# 04-Power_Stage.net
KiCad netlist of a schematic drawn in Altium Designer
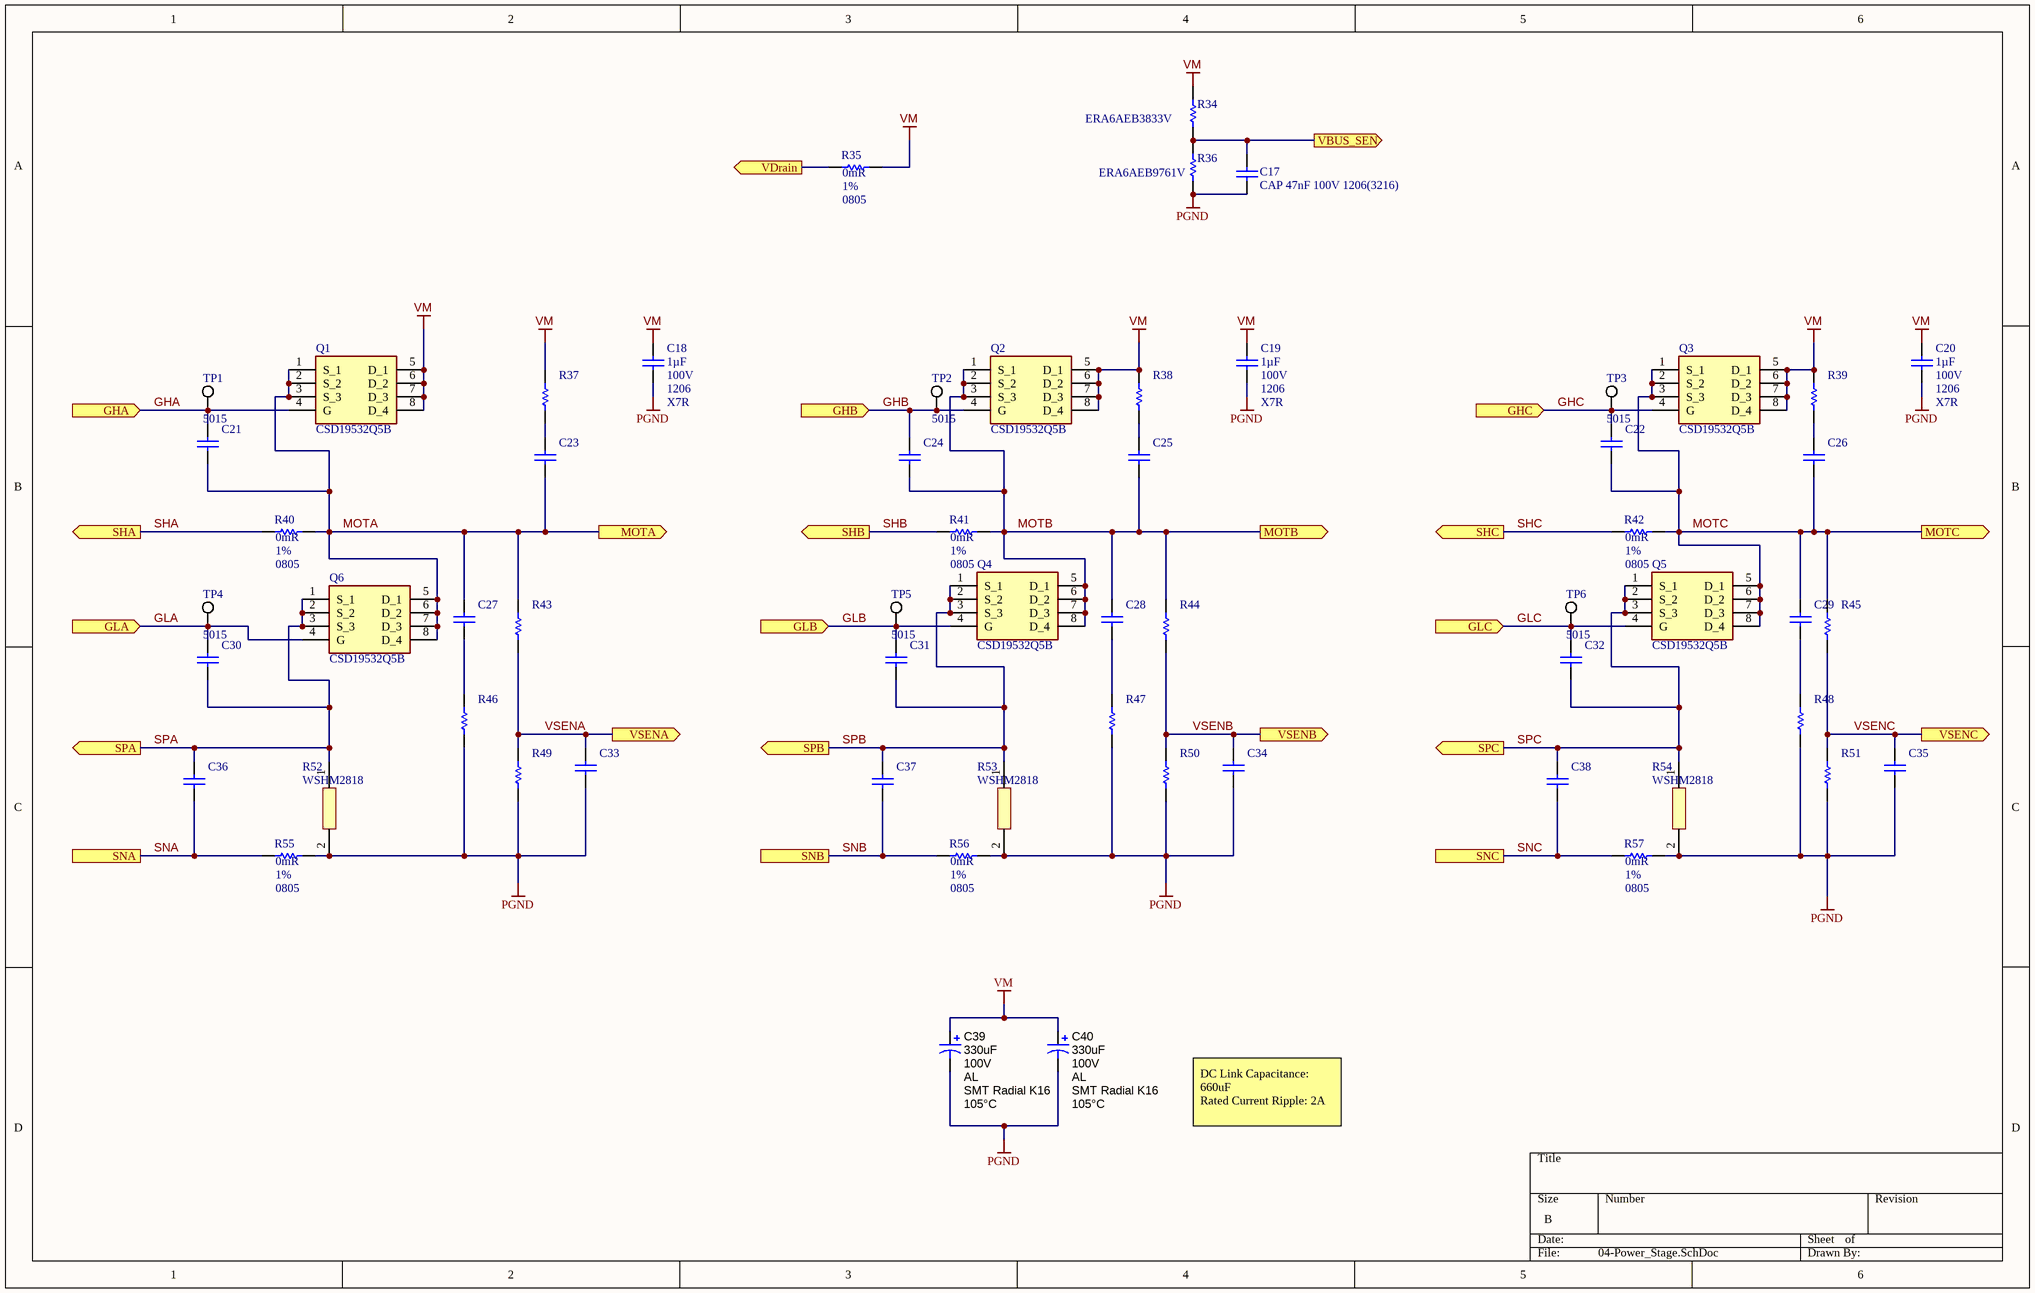
[diagram p0: 04-Power_Stage.SchDoc]

(export (version "E")
  (design (tool "Eeschema 10.0.6"))
  (components
    (comp (ref "C17")
      (value "CAP 47nF 100V 1206(3216)")
      (footprint "CAPC1206(3216)170_N")
      (description "CAP 47nF 100V ±10% 1206 (3216 Metric) Thickness 1.7mm SMD")
      (fields (field (name "TOLERANCE") "Â±10%"))
      (libsource (lib "Altium Content Vault") (part "CAP"))
    )
    (comp (ref "C18")
      (value "C3216X7R2A105K160AA")
      (footprint "CAPC3216X180X20LL20")
      (description "Chip Capacitor, 1 uF, +/- 10%, 100 V, -55 to 125 degC, 1206 (3216 Metric), RoHS, Tape and Reel")
      (fields
        (field (name "CAPACITANCE") "1µF")
        (field (name "MANUFACTURER") "TDK")
        (field (name "PACKAGE REFERENCE") "1206")
        (field (name "VOLTAGE - RATED") "100V")
        (field (name "TOLERANCE") "±10%")
        (field (name "TEMPERATURE COEFFICIENT") "X7R")
      )
      (libsource (lib "Altium Content Vault") (part "CAP-NP-2"))
    )
    (comp (ref "C19")
      (value "C3216X7R2A105K160AA")
      (footprint "CAPC3216X180X20LL20")
      (description "Chip Capacitor, 1 uF, +/- 10%, 100 V, -55 to 125 degC, 1206 (3216 Metric), RoHS, Tape and Reel")
      (fields
        (field (name "CAPACITANCE") "1µF")
        (field (name "MANUFACTURER") "TDK")
        (field (name "PACKAGE REFERENCE") "1206")
        (field (name "VOLTAGE - RATED") "100V")
        (field (name "TOLERANCE") "±10%")
        (field (name "TEMPERATURE COEFFICIENT") "X7R")
      )
      (libsource (lib "Altium Content Vault") (part "CAP-NP-2"))
    )
    (comp (ref "C20")
      (value "C3216X7R2A105K160AA")
      (footprint "CAPC3216X180X20LL20")
      (description "Chip Capacitor, 1 uF, +/- 10%, 100 V, -55 to 125 degC, 1206 (3216 Metric), RoHS, Tape and Reel")
      (fields
        (field (name "CAPACITANCE") "1µF")
        (field (name "MANUFACTURER") "TDK")
        (field (name "PACKAGE REFERENCE") "1206")
        (field (name "VOLTAGE - RATED") "100V")
        (field (name "TOLERANCE") "±10%")
        (field (name "TEMPERATURE COEFFICIENT") "X7R")
      )
      (libsource (lib "Altium Content Vault") (part "CAP-NP-2"))
    )
    (comp (ref "C21")
      (value "GRM188R72A222KA01D")
      (footprint "CAPC1608X90X35NL10T15")
      (fields (field (name "MANUFACTURER") "Murata"))
      (libsource (lib "Altium Content Vault") (part "CAP"))
    )
    (comp (ref "C22")
      (value "GRM188R72A222KA01D")
      (footprint "CAPC1608X90X35NL10T15")
      (fields (field (name "MANUFACTURER") "Murata"))
      (libsource (lib "Altium Content Vault") (part "CAP"))
    )
    (comp (ref "C23")
      (value "GRM188R72A222KA01D")
      (footprint "CAPC1608X90X35NL10T15")
      (fields (field (name "MANUFACTURER") "Murata"))
      (libsource (lib "Altium Content Vault") (part "CAP"))
    )
    (comp (ref "C24")
      (value "GRM188R72A222KA01D")
      (footprint "CAPC1608X90X35NL10T15")
      (fields (field (name "MANUFACTURER") "Murata"))
      (libsource (lib "Altium Content Vault") (part "CAP"))
    )
    (comp (ref "C25")
      (value "GRM188R72A222KA01D")
      (footprint "CAPC1608X90X35NL10T15")
      (fields (field (name "MANUFACTURER") "Murata"))
      (libsource (lib "Altium Content Vault") (part "CAP"))
    )
    (comp (ref "C26")
      (value "GRM188R72A222KA01D")
      (footprint "CAPC1608X90X35NL10T15")
      (fields (field (name "MANUFACTURER") "Murata"))
      (libsource (lib "Altium Content Vault") (part "CAP"))
    )
    (comp (ref "C27")
      (value "GRM188R72A222KA01D")
      (footprint "CAPC1608X90X35NL10T15")
      (fields (field (name "MANUFACTURER") "Murata"))
      (libsource (lib "Altium Content Vault") (part "CAP"))
    )
    (comp (ref "C28")
      (value "GRM188R72A222KA01D")
      (footprint "CAPC1608X90X35NL10T15")
      (fields (field (name "MANUFACTURER") "Murata"))
      (libsource (lib "Altium Content Vault") (part "CAP"))
    )
    (comp (ref "C29")
      (value "GRM188R72A222KA01D")
      (footprint "CAPC1608X90X35NL10T15")
      (fields (field (name "MANUFACTURER") "Murata"))
      (libsource (lib "Altium Content Vault") (part "CAP"))
    )
    (comp (ref "C30")
      (value "GRM188R72A222KA01D")
      (footprint "CAPC1608X90X35NL10T15")
      (fields (field (name "MANUFACTURER") "Murata"))
      (libsource (lib "Altium Content Vault") (part "CAP"))
    )
    (comp (ref "C31")
      (value "GRM188R72A222KA01D")
      (footprint "CAPC1608X90X35NL10T15")
      (fields (field (name "MANUFACTURER") "Murata"))
      (libsource (lib "Altium Content Vault") (part "CAP"))
    )
    (comp (ref "C32")
      (value "GRM188R72A222KA01D")
      (footprint "CAPC1608X90X35NL10T15")
      (fields (field (name "MANUFACTURER") "Murata"))
      (libsource (lib "Altium Content Vault") (part "CAP"))
    )
    (comp (ref "C33")
      (value "06033C473JAT2A")
      (footprint "CAPC1608X90X35NL15T15")
      (fields (field (name "MANUFACTURER") "AVX Interconnect / Elco"))
      (libsource (lib "Altium Content Vault") (part "CAP"))
    )
    (comp (ref "C34")
      (value "06033C473JAT2A")
      (footprint "CAPC1608X90X35NL15T15")
      (fields (field (name "MANUFACTURER") "AVX Interconnect / Elco"))
      (libsource (lib "Altium Content Vault") (part "CAP"))
    )
    (comp (ref "C35")
      (value "06033C473JAT2A")
      (footprint "CAPC1608X90X35NL15T15")
      (fields (field (name "MANUFACTURER") "AVX Interconnect / Elco"))
      (libsource (lib "Altium Content Vault") (part "CAP"))
    )
    (comp (ref "C36")
      (value "0603YC102KAT2A")
      (footprint "CAPC1608X90X35NL15T15")
      (fields (field (name "MANUFACTURER") "AVX Interconnect / Elco"))
      (libsource (lib "Altium Content Vault") (part "CAP"))
    )
    (comp (ref "C37")
      (value "0603YC102KAT2A")
      (footprint "CAPC1608X90X35NL15T15")
      (fields (field (name "MANUFACTURER") "AVX Interconnect / Elco"))
      (libsource (lib "Altium Content Vault") (part "CAP"))
    )
    (comp (ref "C38")
      (value "0603YC102KAT2A")
      (footprint "CAPC1608X90X35NL15T15")
      (fields (field (name "MANUFACTURER") "AVX Interconnect / Elco"))
      (libsource (lib "Altium Content Vault") (part "CAP"))
    )
    (comp (ref "C39")
      (value "EEV-FK2A331M")
      (footprint "SM_RADIAL_K16")
      (description "CAP, AL, 330 uF, 100 V, +/- 20%, 0.153 ohm, AEC-Q200 Grade 2, SMD")
      (fields
        (field (name "TAMAX_C") "105°C")
        (field (name "MANUFACTURER") "Panasonic")
        (field (name "PACKAGEREFERENCE") "SMT Radial K16")
        (field (name "VDC_V") "100V")
        (field (name "TECHNOLOGY") "AL")
        (field (name "VALUEDISPLAYED") "330uF")
        (field (name "PUBLISHER") "Texas Instruments")
      )
      (libsource (lib "driver_board_lib") (part "CMP-0011224-2"))
    )
    (comp (ref "C40")
      (value "EEV-FK2A331M")
      (footprint "SM_RADIAL_K16")
      (description "CAP, AL, 330 uF, 100 V, +/- 20%, 0.153 ohm, AEC-Q200 Grade 2, SMD")
      (fields
        (field (name "TAMAX_C") "105°C")
        (field (name "MANUFACTURER") "Panasonic")
        (field (name "PACKAGEREFERENCE") "SMT Radial K16")
        (field (name "VDC_V") "100V")
        (field (name "TECHNOLOGY") "AL")
        (field (name "VALUEDISPLAYED") "330uF")
        (field (name "PUBLISHER") "Texas Instruments")
      )
      (libsource (lib "driver_board_lib") (part "CMP-0011224-2"))
    )
    (comp (ref "Q1")
      (value "CSD19532Q5B")
      (footprint "SamacSys:Q5B")
      (description "Transistor")
      (fields (field (name "MOUSER PART NUMBER") "595-CSD19532Q5B"))
      (libsource (lib "*") (part "CSD19532Q5B"))
    )
    (comp (ref "Q2")
      (value "CSD19532Q5B")
      (footprint "SamacSys:Q5B")
      (description "Transistor")
      (fields (field (name "MOUSER PART NUMBER") "595-CSD19532Q5B"))
      (libsource (lib "*") (part "CSD19532Q5B"))
    )
    (comp (ref "Q3")
      (value "CSD19532Q5B")
      (footprint "SamacSys:Q5B")
      (description "Transistor")
      (fields (field (name "MOUSER PART NUMBER") "595-CSD19532Q5B"))
      (libsource (lib "*") (part "CSD19532Q5B"))
    )
    (comp (ref "Q4")
      (value "CSD19532Q5B")
      (footprint "SamacSys:Q5B")
      (description "Transistor")
      (fields (field (name "MOUSER PART NUMBER") "595-CSD19532Q5B"))
      (libsource (lib "*") (part "CSD19532Q5B"))
    )
    (comp (ref "Q5")
      (value "CSD19532Q5B")
      (footprint "SamacSys:Q5B")
      (description "Transistor")
      (fields (field (name "MOUSER PART NUMBER") "595-CSD19532Q5B"))
      (libsource (lib "*") (part "CSD19532Q5B"))
    )
    (comp (ref "Q6")
      (value "CSD19532Q5B")
      (footprint "SamacSys:Q5B")
      (description "Transistor")
      (fields (field (name "MOUSER PART NUMBER") "595-CSD19532Q5B"))
      (libsource (lib "*") (part "CSD19532Q5B"))
    )
    (comp (ref "R34")
      (value "ERA6AEB3833V")
      (footprint "RESC2013X60X40LL20T25")
      (fields (field (name "MANUFACTURER") "Panasonic"))
      (libsource (lib "Altium Content Vault") (part "RES"))
    )
    (comp (ref "R35")
      (value "CRCW08050000Z0EA")
      (footprint "RESC2013X50X30LL20T20")
      (fields
        (field (name "MANUFACTURER") "Vishay Dale")
        (field (name "CASE CODE (IMPERIAL)") "0805")
        (field (name "RESISTANCE") "0mR")
        (field (name "TOLERANCE") "1%")
      )
      (libsource (lib "Altium Content Vault") (part "RES"))
    )
    (comp (ref "R36")
      (value "ERA6AEB9761V")
      (footprint "RESC2013X60X40NL20T25")
      (fields (field (name "MANUFACTURER") "Panasonic"))
      (libsource (lib "Altium Content Vault") (part "RES"))
    )
    (comp (ref "R37")
      (value "CRCW08052R70JNEA")
      (footprint "RESC2013X50X30NL20T20")
      (fields (field (name "MANUFACTURER") "Vishay Dale"))
      (libsource (lib "Altium Content Vault") (part "RES"))
    )
    (comp (ref "R38")
      (value "CRCW08052R70JNEA")
      (footprint "RESC2013X50X30NL20T20")
      (fields (field (name "MANUFACTURER") "Vishay Dale"))
      (libsource (lib "Altium Content Vault") (part "RES"))
    )
    (comp (ref "R39")
      (value "CRCW08052R70JNEA")
      (footprint "RESC2013X50X30NL20T20")
      (fields (field (name "MANUFACTURER") "Vishay Dale"))
      (libsource (lib "Altium Content Vault") (part "RES"))
    )
    (comp (ref "R40")
      (value "CRCW08050000Z0EA")
      (footprint "RESC2013X50X30LL20T20")
      (fields
        (field (name "MANUFACTURER") "Vishay Dale")
        (field (name "CASE CODE (IMPERIAL)") "0805")
        (field (name "RESISTANCE") "0mR")
        (field (name "TOLERANCE") "1%")
      )
      (libsource (lib "Altium Content Vault") (part "RES"))
    )
    (comp (ref "R41")
      (value "CRCW08050000Z0EA")
      (footprint "RESC2013X50X30LL20T20")
      (fields
        (field (name "MANUFACTURER") "Vishay Dale")
        (field (name "CASE CODE (IMPERIAL)") "0805")
        (field (name "RESISTANCE") "0mR")
        (field (name "TOLERANCE") "1%")
      )
      (libsource (lib "Altium Content Vault") (part "RES"))
    )
    (comp (ref "R42")
      (value "CRCW08050000Z0EA")
      (footprint "RESC2013X50X30LL20T20")
      (fields
        (field (name "MANUFACTURER") "Vishay Dale")
        (field (name "CASE CODE (IMPERIAL)") "0805")
        (field (name "RESISTANCE") "0mR")
        (field (name "TOLERANCE") "1%")
      )
      (libsource (lib "Altium Content Vault") (part "RES"))
    )
    (comp (ref "R43")
      (value "CRCW0603383KFKEA")
      (footprint "RESC1609X50X30ML10T20")
      (fields (field (name "MANUFACTURER") "Vishay Dale"))
      (libsource (lib "Altium Content Vault") (part "RES"))
    )
    (comp (ref "R44")
      (value "CRCW0603383KFKEA")
      (footprint "RESC1609X50X30ML10T20")
      (fields (field (name "MANUFACTURER") "Vishay Dale"))
      (libsource (lib "Altium Content Vault") (part "RES"))
    )
    (comp (ref "R45")
      (value "CRCW0603383KFKEA")
      (footprint "RESC1609X50X30ML10T20")
      (fields (field (name "MANUFACTURER") "Vishay Dale"))
      (libsource (lib "Altium Content Vault") (part "RES"))
    )
    (comp (ref "R46")
      (value "CRCW08052R70JNEA")
      (footprint "RESC2013X50X30NL20T20")
      (fields (field (name "MANUFACTURER") "Vishay Dale"))
      (libsource (lib "Altium Content Vault") (part "RES"))
    )
    (comp (ref "R47")
      (value "CRCW08052R70JNEA")
      (footprint "RESC2013X50X30NL20T20")
      (fields (field (name "MANUFACTURER") "Vishay Dale"))
      (libsource (lib "Altium Content Vault") (part "RES"))
    )
    (comp (ref "R48")
      (value "CRCW08052R70JNEA")
      (footprint "RESC2013X50X30NL20T20")
      (fields (field (name "MANUFACTURER") "Vishay Dale"))
      (libsource (lib "Altium Content Vault") (part "RES"))
    )
    (comp (ref "R49")
      (value "RC0603FR-079K76L")
      (footprint "RESC1608X55X25NL10T15")
      (fields (field (name "MANUFACTURER") "Yageo"))
      (libsource (lib "Altium Content Vault") (part "RES"))
    )
    (comp (ref "R50")
      (value "RC0603FR-079K76L")
      (footprint "RESC1608X55X25NL10T15")
      (fields (field (name "MANUFACTURER") "Yageo"))
      (libsource (lib "Altium Content Vault") (part "RES"))
    )
    (comp (ref "R51")
      (value "RC0603FR-079K76L")
      (footprint "RESC1608X55X25NL10T15")
      (fields (field (name "MANUFACTURER") "Yageo"))
      (libsource (lib "Altium Content Vault") (part "RES"))
    )
    (comp (ref "R52")
      (value "WSHM2818")
      (footprint "WSHM2818:PCBComponent_1")
      (libsource (lib "WSHM2818") (part "WSHM2818"))
    )
    (comp (ref "R53")
      (value "WSHM2818")
      (footprint "WSHM2818:PCBComponent_1")
      (libsource (lib "WSHM2818") (part "WSHM2818"))
    )
    (comp (ref "R54")
      (value "WSHM2818")
      (footprint "WSHM2818:PCBComponent_1")
      (libsource (lib "WSHM2818") (part "WSHM2818"))
    )
    (comp (ref "R55")
      (value "CRCW08050000Z0EA")
      (footprint "RESC2013X50X30LL20T20")
      (fields
        (field (name "MANUFACTURER") "Vishay Dale")
        (field (name "CASE CODE (IMPERIAL)") "0805")
        (field (name "RESISTANCE") "0mR")
        (field (name "TOLERANCE") "1%")
      )
      (libsource (lib "Altium Content Vault") (part "RES"))
    )
    (comp (ref "R56")
      (value "CRCW08050000Z0EA")
      (footprint "RESC2013X50X30LL20T20")
      (fields
        (field (name "MANUFACTURER") "Vishay Dale")
        (field (name "CASE CODE (IMPERIAL)") "0805")
        (field (name "RESISTANCE") "0mR")
        (field (name "TOLERANCE") "1%")
      )
      (libsource (lib "Altium Content Vault") (part "RES"))
    )
    (comp (ref "R57")
      (value "CRCW08050000Z0EA")
      (footprint "RESC2013X50X30LL20T20")
      (fields
        (field (name "MANUFACTURER") "Vishay Dale")
        (field (name "CASE CODE (IMPERIAL)") "0805")
        (field (name "RESISTANCE") "0mR")
        (field (name "TOLERANCE") "1%")
      )
      (libsource (lib "Altium Content Vault") (part "RES"))
    )
    (comp (ref "TP1")
      (value "5015")
      (footprint "KSTN-5015_V")
      (description "Test Point, White, SMT")
      (fields (field (name "MANUFACTURER") "Keystone"))
      (libsource (lib "Altium Content Vault") (part "TESTPOINT_WHITE"))
    )
    (comp (ref "TP2")
      (value "5015")
      (footprint "KSTN-5015_V")
      (description "Test Point, White, SMT")
      (fields (field (name "MANUFACTURER") "Keystone"))
      (libsource (lib "Altium Content Vault") (part "TESTPOINT_WHITE"))
    )
    (comp (ref "TP3")
      (value "5015")
      (footprint "KSTN-5015_V")
      (description "Test Point, White, SMT")
      (fields (field (name "MANUFACTURER") "Keystone"))
      (libsource (lib "Altium Content Vault") (part "TESTPOINT_WHITE"))
    )
    (comp (ref "TP4")
      (value "5015")
      (footprint "KSTN-5015_V")
      (description "Test Point, White, SMT")
      (fields (field (name "MANUFACTURER") "Keystone"))
      (libsource (lib "Altium Content Vault") (part "TESTPOINT_WHITE"))
    )
    (comp (ref "TP5")
      (value "5015")
      (footprint "KSTN-5015_V")
      (description "Test Point, White, SMT")
      (fields (field (name "MANUFACTURER") "Keystone"))
      (libsource (lib "Altium Content Vault") (part "TESTPOINT_WHITE"))
    )
    (comp (ref "TP6")
      (value "5015")
      (footprint "KSTN-5015_V")
      (description "Test Point, White, SMT")
      (fields (field (name "MANUFACTURER") "Keystone"))
      (libsource (lib "Altium Content Vault") (part "TESTPOINT_WHITE"))
    )
  )
  (nets
    (net (code "1") (name "/GHA") (class "Default")
      (node (ref "C21") (pin "2") (pinfunction "2_2") (pintype "passive"))
      (node (ref "Q1") (pin "4") (pinfunction "G_4") (pintype "passive"))
      (node (ref "TP1") (pin "1") (pinfunction "1_1") (pintype "passive"))
    )
    (net (code "2") (name "/GHB") (class "Default")
      (node (ref "C24") (pin "2") (pinfunction "2_2") (pintype "passive"))
      (node (ref "Q2") (pin "4") (pinfunction "G_4") (pintype "passive"))
      (node (ref "TP2") (pin "1") (pinfunction "1_1") (pintype "passive"))
    )
    (net (code "3") (name "/GHC") (class "Default")
      (node (ref "C22") (pin "2") (pinfunction "2_2") (pintype "passive"))
      (node (ref "Q3") (pin "4") (pinfunction "G_4") (pintype "passive"))
      (node (ref "TP3") (pin "1") (pinfunction "1_1") (pintype "passive"))
    )
    (net (code "4") (name "/GLA") (class "Default")
      (node (ref "C30") (pin "2") (pinfunction "2_2") (pintype "passive"))
      (node (ref "Q6") (pin "4") (pinfunction "G_4") (pintype "passive"))
      (node (ref "TP4") (pin "1") (pinfunction "1_1") (pintype "passive"))
    )
    (net (code "5") (name "/GLB") (class "Default")
      (node (ref "C31") (pin "2") (pinfunction "2_2") (pintype "passive"))
      (node (ref "Q4") (pin "4") (pinfunction "G_4") (pintype "passive"))
      (node (ref "TP5") (pin "1") (pinfunction "1_1") (pintype "passive"))
    )
    (net (code "6") (name "/GLC") (class "Default")
      (node (ref "C32") (pin "2") (pinfunction "2_2") (pintype "passive"))
      (node (ref "Q5") (pin "4") (pinfunction "G_4") (pintype "passive"))
      (node (ref "TP6") (pin "1") (pinfunction "1_1") (pintype "passive"))
    )
    (net (code "7") (name "/MOTA") (class "Default")
      (node (ref "C21") (pin "1") (pinfunction "1_1") (pintype "passive"))
      (node (ref "C23") (pin "1") (pinfunction "1_1") (pintype "passive"))
      (node (ref "C27") (pin "2") (pinfunction "2_2") (pintype "passive"))
      (node (ref "Q1") (pin "1") (pinfunction "S_1_1") (pintype "passive"))
      (node (ref "Q1") (pin "2") (pinfunction "S_2_2") (pintype "passive"))
      (node (ref "Q1") (pin "3") (pinfunction "S_3_3") (pintype "passive"))
      (node (ref "Q6") (pin "5") (pinfunction "D_1_5") (pintype "passive"))
      (node (ref "Q6") (pin "6") (pinfunction "D_2_6") (pintype "passive"))
      (node (ref "Q6") (pin "7") (pinfunction "D_3_7") (pintype "passive"))
      (node (ref "Q6") (pin "8") (pinfunction "D_4_8") (pintype "passive"))
      (node (ref "R40") (pin "2") (pinfunction "2_2") (pintype "passive"))
      (node (ref "R43") (pin "2") (pinfunction "2_2") (pintype "passive"))
    )
    (net (code "8") (name "/MOTB") (class "Default")
      (node (ref "C24") (pin "1") (pinfunction "1_1") (pintype "passive"))
      (node (ref "C25") (pin "1") (pinfunction "1_1") (pintype "passive"))
      (node (ref "C28") (pin "2") (pinfunction "2_2") (pintype "passive"))
      (node (ref "Q2") (pin "1") (pinfunction "S_1_1") (pintype "passive"))
      (node (ref "Q2") (pin "2") (pinfunction "S_2_2") (pintype "passive"))
      (node (ref "Q2") (pin "3") (pinfunction "S_3_3") (pintype "passive"))
      (node (ref "Q4") (pin "5") (pinfunction "D_1_5") (pintype "passive"))
      (node (ref "Q4") (pin "6") (pinfunction "D_2_6") (pintype "passive"))
      (node (ref "Q4") (pin "7") (pinfunction "D_3_7") (pintype "passive"))
      (node (ref "Q4") (pin "8") (pinfunction "D_4_8") (pintype "passive"))
      (node (ref "R41") (pin "2") (pinfunction "2_2") (pintype "passive"))
      (node (ref "R44") (pin "2") (pinfunction "2_2") (pintype "passive"))
    )
    (net (code "9") (name "/MOTC") (class "Default")
      (node (ref "C22") (pin "1") (pinfunction "1_1") (pintype "passive"))
      (node (ref "C26") (pin "1") (pinfunction "1_1") (pintype "passive"))
      (node (ref "C29") (pin "2") (pinfunction "2_2") (pintype "passive"))
      (node (ref "Q3") (pin "1") (pinfunction "S_1_1") (pintype "passive"))
      (node (ref "Q3") (pin "2") (pinfunction "S_2_2") (pintype "passive"))
      (node (ref "Q3") (pin "3") (pinfunction "S_3_3") (pintype "passive"))
      (node (ref "Q5") (pin "5") (pinfunction "D_1_5") (pintype "passive"))
      (node (ref "Q5") (pin "6") (pinfunction "D_2_6") (pintype "passive"))
      (node (ref "Q5") (pin "7") (pinfunction "D_3_7") (pintype "passive"))
      (node (ref "Q5") (pin "8") (pinfunction "D_4_8") (pintype "passive"))
      (node (ref "R42") (pin "2") (pinfunction "2_2") (pintype "passive"))
      (node (ref "R45") (pin "2") (pinfunction "2_2") (pintype "passive"))
    )
    (net (code "10") (name "/SHA") (class "Default")
      (node (ref "R40") (pin "1") (pinfunction "1_1") (pintype "passive"))
    )
    (net (code "11") (name "/SHB") (class "Default")
      (node (ref "R41") (pin "1") (pinfunction "1_1") (pintype "passive"))
    )
    (net (code "12") (name "/SHC") (class "Default")
      (node (ref "R42") (pin "1") (pinfunction "1_1") (pintype "passive"))
    )
    (net (code "13") (name "/SNA") (class "Default")
      (node (ref "C36") (pin "1") (pinfunction "1_1") (pintype "passive"))
      (node (ref "R55") (pin "1") (pinfunction "1_1") (pintype "passive"))
    )
    (net (code "14") (name "/SNB") (class "Default")
      (node (ref "C37") (pin "1") (pinfunction "1_1") (pintype "passive"))
      (node (ref "R56") (pin "1") (pinfunction "1_1") (pintype "passive"))
    )
    (net (code "15") (name "/SNC") (class "Default")
      (node (ref "C38") (pin "1") (pinfunction "1_1") (pintype "passive"))
      (node (ref "R57") (pin "1") (pinfunction "1_1") (pintype "passive"))
    )
    (net (code "16") (name "/SPA") (class "Default")
      (node (ref "C30") (pin "1") (pinfunction "1_1") (pintype "passive"))
      (node (ref "C36") (pin "2") (pinfunction "2_2") (pintype "passive"))
      (node (ref "Q6") (pin "1") (pinfunction "S_1_1") (pintype "passive"))
      (node (ref "Q6") (pin "2") (pinfunction "S_2_2") (pintype "passive"))
      (node (ref "Q6") (pin "3") (pinfunction "S_3_3") (pintype "passive"))
      (node (ref "R52") (pin "1") (pinfunction "1_1") (pintype "passive"))
    )
    (net (code "17") (name "/SPB") (class "Default")
      (node (ref "C31") (pin "1") (pinfunction "1_1") (pintype "passive"))
      (node (ref "C37") (pin "2") (pinfunction "2_2") (pintype "passive"))
      (node (ref "Q4") (pin "1") (pinfunction "S_1_1") (pintype "passive"))
      (node (ref "Q4") (pin "2") (pinfunction "S_2_2") (pintype "passive"))
      (node (ref "Q4") (pin "3") (pinfunction "S_3_3") (pintype "passive"))
      (node (ref "R53") (pin "1") (pinfunction "1_1") (pintype "passive"))
    )
    (net (code "18") (name "/SPC") (class "Default")
      (node (ref "C32") (pin "1") (pinfunction "1_1") (pintype "passive"))
      (node (ref "C38") (pin "2") (pinfunction "2_2") (pintype "passive"))
      (node (ref "Q5") (pin "1") (pinfunction "S_1_1") (pintype "passive"))
      (node (ref "Q5") (pin "2") (pinfunction "S_2_2") (pintype "passive"))
      (node (ref "Q5") (pin "3") (pinfunction "S_3_3") (pintype "passive"))
      (node (ref "R54") (pin "1") (pinfunction "1_1") (pintype "passive"))
    )
    (net (code "19") (name "/VBUS_SEN") (class "Default")
      (node (ref "C17") (pin "2") (pinfunction "2_2") (pintype "passive"))
      (node (ref "R34") (pin "1") (pinfunction "1_1") (pintype "passive"))
      (node (ref "R36") (pin "2") (pinfunction "2_2") (pintype "passive"))
    )
    (net (code "20") (name "/VDrain") (class "Default")
      (node (ref "R35") (pin "1") (pinfunction "1_1") (pintype "passive"))
    )
    (net (code "21") (name "/VSENA") (class "Default")
      (node (ref "C33") (pin "2") (pinfunction "2_2") (pintype "passive"))
      (node (ref "R43") (pin "1") (pinfunction "1_1") (pintype "passive"))
      (node (ref "R49") (pin "1") (pinfunction "1_1") (pintype "passive"))
    )
    (net (code "22") (name "/VSENB") (class "Default")
      (node (ref "C34") (pin "2") (pinfunction "2_2") (pintype "passive"))
      (node (ref "R44") (pin "1") (pinfunction "1_1") (pintype "passive"))
      (node (ref "R50") (pin "1") (pinfunction "1_1") (pintype "passive"))
    )
    (net (code "23") (name "/VSENC") (class "Default")
      (node (ref "C35") (pin "2") (pinfunction "2_2") (pintype "passive"))
      (node (ref "R45") (pin "1") (pinfunction "1_1") (pintype "passive"))
      (node (ref "R51") (pin "1") (pinfunction "1_1") (pintype "passive"))
    )
    (net (code "24") (name "Net-(C23-Pad2)") (class "Default")
      (node (ref "C23") (pin "2") (pinfunction "2_2") (pintype "passive"))
      (node (ref "R37") (pin "1") (pinfunction "1_1") (pintype "passive"))
    )
    (net (code "25") (name "Net-(C25-Pad2)") (class "Default")
      (node (ref "C25") (pin "2") (pinfunction "2_2") (pintype "passive"))
      (node (ref "R38") (pin "1") (pinfunction "1_1") (pintype "passive"))
    )
    (net (code "26") (name "Net-(C26-Pad2)") (class "Default")
      (node (ref "C26") (pin "2") (pinfunction "2_2") (pintype "passive"))
      (node (ref "R39") (pin "1") (pinfunction "1_1") (pintype "passive"))
    )
    (net (code "27") (name "Net-(C27-Pad1)") (class "Default")
      (node (ref "C27") (pin "1") (pinfunction "1_1") (pintype "passive"))
      (node (ref "R46") (pin "2") (pinfunction "2_2") (pintype "passive"))
    )
    (net (code "28") (name "Net-(C28-Pad1)") (class "Default")
      (node (ref "C28") (pin "1") (pinfunction "1_1") (pintype "passive"))
      (node (ref "R47") (pin "2") (pinfunction "2_2") (pintype "passive"))
    )
    (net (code "29") (name "Net-(C29-Pad1)") (class "Default")
      (node (ref "C29") (pin "1") (pinfunction "1_1") (pintype "passive"))
      (node (ref "R48") (pin "2") (pinfunction "2_2") (pintype "passive"))
    )
    (net (code "30") (name "PGND") (class "Default")
      (node (ref "C17") (pin "1") (pinfunction "1_1") (pintype "passive"))
      (node (ref "C18") (pin "1") (pinfunction "1_1") (pintype "passive"))
      (node (ref "C19") (pin "1") (pinfunction "1_1") (pintype "passive"))
      (node (ref "C20") (pin "1") (pinfunction "1_1") (pintype "passive"))
      (node (ref "C33") (pin "1") (pinfunction "1_1") (pintype "passive"))
      (node (ref "C34") (pin "1") (pinfunction "1_1") (pintype "passive"))
      (node (ref "C35") (pin "1") (pinfunction "1_1") (pintype "passive"))
      (node (ref "C39") (pin "2") (pinfunction "-_2") (pintype "passive"))
      (node (ref "C40") (pin "2") (pinfunction "-_2") (pintype "passive"))
      (node (ref "R36") (pin "1") (pinfunction "1_1") (pintype "passive"))
      (node (ref "R46") (pin "1") (pinfunction "1_1") (pintype "passive"))
      (node (ref "R47") (pin "1") (pinfunction "1_1") (pintype "passive"))
      (node (ref "R48") (pin "1") (pinfunction "1_1") (pintype "passive"))
      (node (ref "R49") (pin "2") (pinfunction "2_2") (pintype "passive"))
      (node (ref "R50") (pin "2") (pinfunction "2_2") (pintype "passive"))
      (node (ref "R51") (pin "2") (pinfunction "2_2") (pintype "passive"))
      (node (ref "R52") (pin "2") (pinfunction "2_2") (pintype "passive"))
      (node (ref "R53") (pin "2") (pinfunction "2_2") (pintype "passive"))
      (node (ref "R54") (pin "2") (pinfunction "2_2") (pintype "passive"))
      (node (ref "R55") (pin "2") (pinfunction "2_2") (pintype "passive"))
      (node (ref "R56") (pin "2") (pinfunction "2_2") (pintype "passive"))
      (node (ref "R57") (pin "2") (pinfunction "2_2") (pintype "passive"))
    )
    (net (code "31") (name "VM") (class "Default")
      (node (ref "C18") (pin "2") (pinfunction "2_2") (pintype "passive"))
      (node (ref "C19") (pin "2") (pinfunction "2_2") (pintype "passive"))
      (node (ref "C20") (pin "2") (pinfunction "2_2") (pintype "passive"))
      (node (ref "C39") (pin "1") (pinfunction "+_1") (pintype "passive"))
      (node (ref "C40") (pin "1") (pinfunction "+_1") (pintype "passive"))
      (node (ref "Q1") (pin "5") (pinfunction "D_1_5") (pintype "passive"))
      (node (ref "Q1") (pin "6") (pinfunction "D_2_6") (pintype "passive"))
      (node (ref "Q1") (pin "7") (pinfunction "D_3_7") (pintype "passive"))
      (node (ref "Q1") (pin "8") (pinfunction "D_4_8") (pintype "passive"))
      (node (ref "Q2") (pin "5") (pinfunction "D_1_5") (pintype "passive"))
      (node (ref "Q2") (pin "6") (pinfunction "D_2_6") (pintype "passive"))
      (node (ref "Q2") (pin "7") (pinfunction "D_3_7") (pintype "passive"))
      (node (ref "Q2") (pin "8") (pinfunction "D_4_8") (pintype "passive"))
      (node (ref "Q3") (pin "5") (pinfunction "D_1_5") (pintype "passive"))
      (node (ref "Q3") (pin "6") (pinfunction "D_2_6") (pintype "passive"))
      (node (ref "Q3") (pin "7") (pinfunction "D_3_7") (pintype "passive"))
      (node (ref "Q3") (pin "8") (pinfunction "D_4_8") (pintype "passive"))
      (node (ref "R34") (pin "2") (pinfunction "2_2") (pintype "passive"))
      (node (ref "R35") (pin "2") (pinfunction "2_2") (pintype "passive"))
      (node (ref "R37") (pin "2") (pinfunction "2_2") (pintype "passive"))
      (node (ref "R38") (pin "2") (pinfunction "2_2") (pintype "passive"))
      (node (ref "R39") (pin "2") (pinfunction "2_2") (pintype "passive"))
    )
  )
)
